# AS_Node_Outputs.net
KiCad netlist of a schematic drawn in Altium Designer
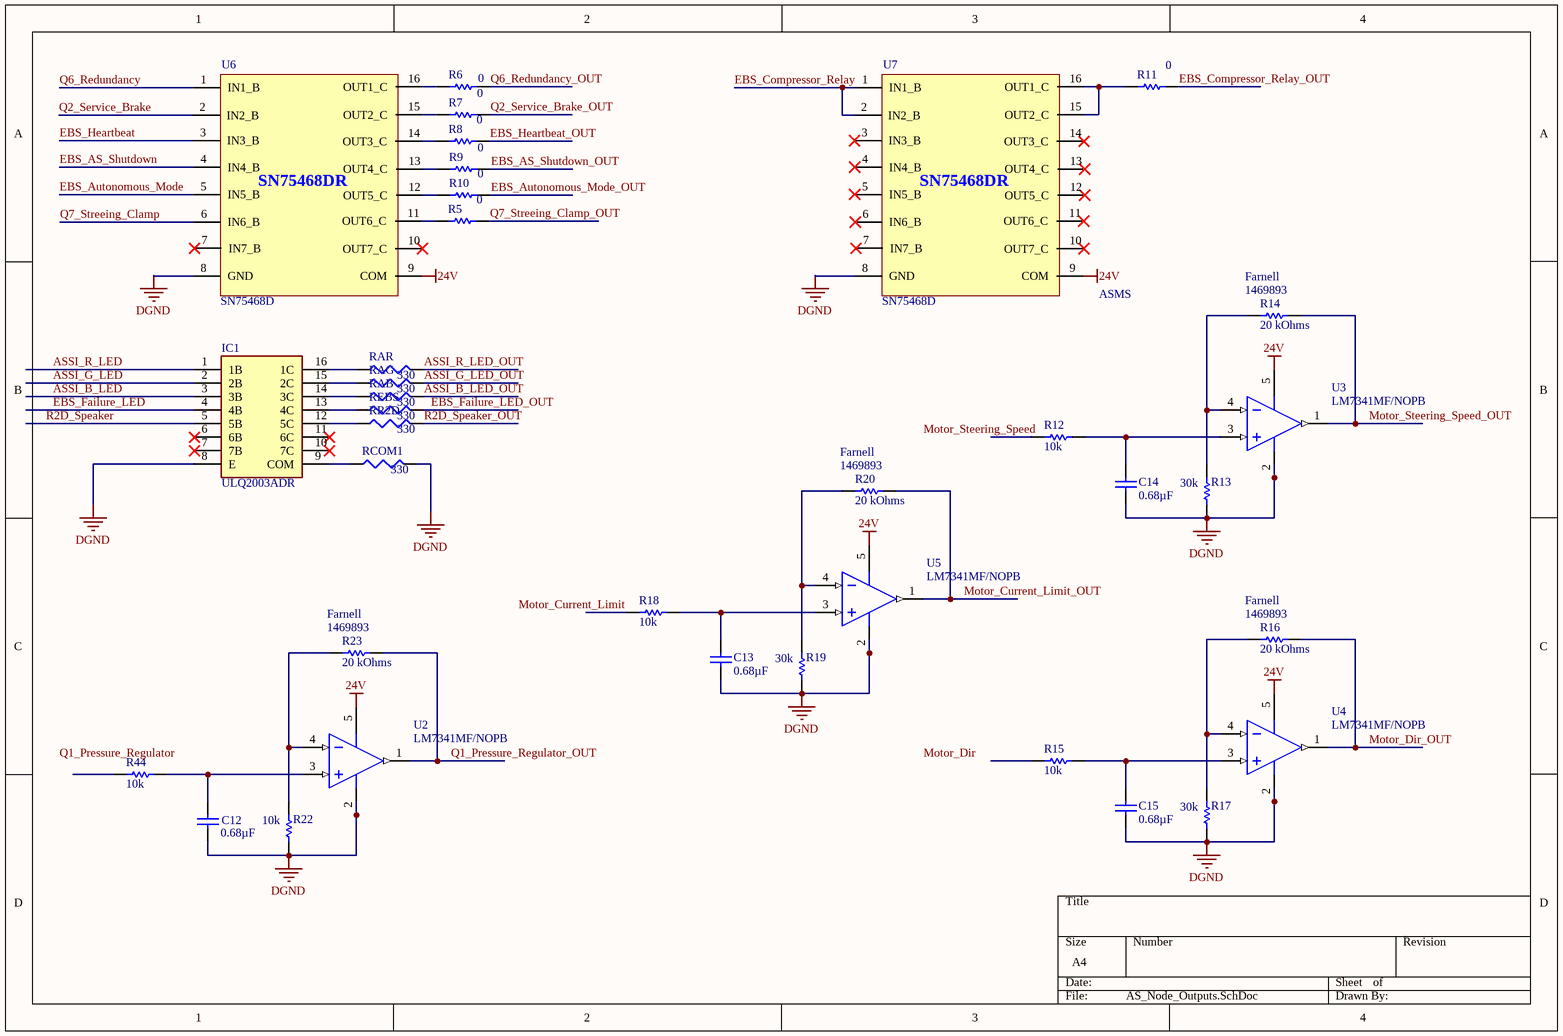
[diagram p0: AS_Node_Outputs.SchDoc]

(export (version "E")
  (design (tool "Eeschema 10.0.6"))
  (components
    (comp (ref "C12")
      (value "0.68µF")
      (footprint "dV_C0805")
      (fields
        (field (name "MANUFACTURER") "KEMET")
        (field (name "MANUFACTURER PART NUMBER") "C0805C684J3NACTU")
      )
      (libsource (lib "altium-import") (part "root_1_Cap_"))
    )
    (comp (ref "C13")
      (value "0.68µF")
      (footprint "dV_C0805")
      (fields
        (field (name "MANUFACTURER") "KEMET")
        (field (name "MANUFACTURER PART NUMBER") "C0805C684J3NACTU")
      )
      (libsource (lib "altium-import") (part "root_1_Cap_"))
    )
    (comp (ref "C14")
      (value "0.68µF")
      (footprint "dV_C0805")
      (fields
        (field (name "MANUFACTURER") "KEMET")
        (field (name "MANUFACTURER PART NUMBER") "C0805C684J3NACTU")
      )
      (libsource (lib "altium-import") (part "root_1_Cap_"))
    )
    (comp (ref "C15")
      (value "0.68µF")
      (footprint "dV_C0805")
      (fields
        (field (name "MANUFACTURER") "KEMET")
        (field (name "MANUFACTURER PART NUMBER") "C0805C684J3NACTU")
      )
      (libsource (lib "altium-import") (part "root_1_Cap_"))
    )
    (comp (ref "IC1")
      (value "ULQ2003ADR")
      (footprint "SamacSys:SOIC127P600X175-16N")
      (description "Integrated Circuit")
      (fields (field (name "MOUSER PART NUMBER") "595-ULQ2003ADR") (field (name "RS PART NUMBER") "6658696P"))
      (libsource (lib "*") (part "ULQ2003ADR"))
    )
    (comp (ref "R5")
      (value "0")
      (footprint "dV_R0805")
      (fields
        (field (name "MANUFACTURER") "PANASONIC ELECTRONIC COMPONENTS")
        (field (name "MANUFACTURER PART NUMBER") "ERJ6GEY0R00V")
      )
      (libsource (lib "altium-import") (part "root_0_Res1_"))
    )
    (comp (ref "R6")
      (value "0")
      (footprint "dV_R0805")
      (fields
        (field (name "MANUFACTURER") "PANASONIC ELECTRONIC COMPONENTS")
        (field (name "MANUFACTURER PART NUMBER") "ERJ6GEY0R00V")
      )
      (libsource (lib "altium-import") (part "root_0_Res1_"))
    )
    (comp (ref "R7")
      (value "0")
      (footprint "dV_R0805")
      (fields
        (field (name "MANUFACTURER") "PANASONIC ELECTRONIC COMPONENTS")
        (field (name "MANUFACTURER PART NUMBER") "ERJ6GEY0R00V")
      )
      (libsource (lib "altium-import") (part "root_0_Res1_"))
    )
    (comp (ref "R8")
      (value "0")
      (footprint "dV_R0805")
      (fields
        (field (name "MANUFACTURER") "PANASONIC ELECTRONIC COMPONENTS")
        (field (name "MANUFACTURER PART NUMBER") "ERJ6GEY0R00V")
      )
      (libsource (lib "altium-import") (part "root_0_Res1_"))
    )
    (comp (ref "R9")
      (value "0")
      (footprint "dV_R0805")
      (fields
        (field (name "MANUFACTURER") "PANASONIC ELECTRONIC COMPONENTS")
        (field (name "MANUFACTURER PART NUMBER") "ERJ6GEY0R00V")
      )
      (libsource (lib "altium-import") (part "root_0_Res1_"))
    )
    (comp (ref "R10")
      (value "0")
      (footprint "dV_R0805")
      (fields
        (field (name "MANUFACTURER") "PANASONIC ELECTRONIC COMPONENTS")
        (field (name "MANUFACTURER PART NUMBER") "ERJ6GEY0R00V")
      )
      (libsource (lib "altium-import") (part "root_0_Res1_"))
    )
    (comp (ref "R11")
      (value "0")
      (footprint "dV_R0805")
      (fields
        (field (name "MANUFACTURER") "PANASONIC ELECTRONIC COMPONENTS")
        (field (name "MANUFACTURER PART NUMBER") "ERJ6GEY0R00V")
      )
      (libsource (lib "altium-import") (part "root_0_Res1_"))
    )
    (comp (ref "R12")
      (value "10k")
      (footprint "dV_R0805")
      (fields
        (field (name "MANUFACTURER") "PANASONIC ELECTRONIC COMPONENTS")
        (field (name "MANUFACTURER PART NUMBER") "ERA6AEB103V")
      )
      (libsource (lib "altium-import") (part "root_0_Res1_"))
    )
    (comp (ref "R13")
      (value "30k")
      (footprint "dV_R0805")
      (fields
        (field (name "MANUFACTURER") "Panasonic")
        (field (name "MANUFACTURER PART NUMBER") "ERA-6AEB303V")
      )
      (libsource (lib "altium-import") (part "root_3_Res1_"))
    )
    (comp (ref "R14")
      (value "20 kOhms")
      (footprint "dV_R0805")
      (fields
        (field (name "MANUFACTURER PART NUMBER") "CRCW080520K0FKEA")
        (field (name "MANUFACTURER") "Vishay")
        (field (name "SUPPLIER PART NUMBER") "1469893")
        (field (name "TOLERANCE") "1 %")
        (field (name "SUPPLIER") "Farnell")
      )
      (libsource (lib "altium-import") (part "root_0_Res1_"))
    )
    (comp (ref "R15")
      (value "10k")
      (footprint "dV_R0805")
      (fields
        (field (name "MANUFACTURER") "PANASONIC ELECTRONIC COMPONENTS")
        (field (name "MANUFACTURER PART NUMBER") "ERA6AEB103V")
      )
      (libsource (lib "altium-import") (part "root_0_Res1_"))
    )
    (comp (ref "R16")
      (value "20 kOhms")
      (footprint "dV_R0805")
      (fields
        (field (name "MANUFACTURER PART NUMBER") "CRCW080520K0FKEA")
        (field (name "MANUFACTURER") "Vishay")
        (field (name "SUPPLIER PART NUMBER") "1469893")
        (field (name "TOLERANCE") "1 %")
        (field (name "SUPPLIER") "Farnell")
      )
      (libsource (lib "altium-import") (part "root_0_Res1_"))
    )
    (comp (ref "R17")
      (value "30k")
      (footprint "dV_R0805")
      (fields
        (field (name "MANUFACTURER") "Panasonic")
        (field (name "MANUFACTURER PART NUMBER") "ERA-6AEB303V")
      )
      (libsource (lib "altium-import") (part "root_3_Res1_"))
    )
    (comp (ref "R18")
      (value "10k")
      (footprint "dV_R0805")
      (fields
        (field (name "MANUFACTURER") "PANASONIC ELECTRONIC COMPONENTS")
        (field (name "MANUFACTURER PART NUMBER") "ERA6AEB103V")
      )
      (libsource (lib "altium-import") (part "root_0_Res1_"))
    )
    (comp (ref "R19")
      (value "30k")
      (footprint "dV_R0805")
      (fields
        (field (name "MANUFACTURER") "Panasonic")
        (field (name "MANUFACTURER PART NUMBER") "ERA-6AEB303V")
      )
      (libsource (lib "altium-import") (part "root_3_Res1_"))
    )
    (comp (ref "R20")
      (value "20 kOhms")
      (footprint "dV_R0805")
      (fields
        (field (name "MANUFACTURER PART NUMBER") "CRCW080520K0FKEA")
        (field (name "MANUFACTURER") "Vishay")
        (field (name "SUPPLIER PART NUMBER") "1469893")
        (field (name "TOLERANCE") "1 %")
        (field (name "SUPPLIER") "Farnell")
      )
      (libsource (lib "altium-import") (part "root_0_Res1_"))
    )
    (comp (ref "R22")
      (value "10k")
      (footprint "dV_R0805")
      (fields
        (field (name "MANUFACTURER") "PANASONIC ELECTRONIC COMPONENTS")
        (field (name "MANUFACTURER PART NUMBER") "ERA6AEB103V")
      )
      (libsource (lib "altium-import") (part "root_3_Res1_"))
    )
    (comp (ref "R23")
      (value "20 kOhms")
      (footprint "dV_R0805")
      (fields
        (field (name "MANUFACTURER PART NUMBER") "CRCW080520K0FKEA")
        (field (name "MANUFACTURER") "Vishay")
        (field (name "SUPPLIER PART NUMBER") "1469893")
        (field (name "TOLERANCE") "1 %")
        (field (name "SUPPLIER") "Farnell")
      )
      (libsource (lib "altium-import") (part "root_0_Res1_"))
    )
    (comp (ref "R44")
      (value "10k")
      (footprint "dV_R0805")
      (fields
        (field (name "MANUFACTURER") "PANASONIC ELECTRONIC COMPONENTS")
        (field (name "MANUFACTURER PART NUMBER") "ERA6AEB103V")
      )
      (libsource (lib "altium-import") (part "root_0_Res1_"))
    )
    (comp (ref "RAB")
      (value "330")
      (footprint "SMD-0805-RES")
      (description "Resistor")
      (fields (field (name "Comment") "Res3") (field (name "PUBLISHER") "Altium Limited"))
      (libsource (lib "Miscellaneous Devices") (part "Res3"))
    )
    (comp (ref "RAG")
      (value "330")
      (footprint "SMD-0805-RES")
      (description "Resistor")
      (fields (field (name "Comment") "Res3") (field (name "PUBLISHER") "Altium Limited"))
      (libsource (lib "Miscellaneous Devices") (part "Res3"))
    )
    (comp (ref "RAR")
      (value "330")
      (footprint "SMD-0805-RES")
      (description "Resistor")
      (fields (field (name "Comment") "Res3") (field (name "PUBLISHER") "Altium Limited"))
      (libsource (lib "Miscellaneous Devices") (part "Res3"))
    )
    (comp (ref "RCOM1")
      (value "330")
      (footprint "SMD-0805-RES")
      (description "Resistor")
      (fields (field (name "Comment") "Res3") (field (name "PUBLISHER") "Altium Limited"))
      (libsource (lib "Miscellaneous Devices") (part "Res3"))
    )
    (comp (ref "REBS")
      (value "330")
      (footprint "SMD-0805-RES")
      (description "Resistor")
      (fields (field (name "Comment") "Res3") (field (name "PUBLISHER") "Altium Limited"))
      (libsource (lib "Miscellaneous Devices") (part "Res3"))
    )
    (comp (ref "RR2D")
      (value "330")
      (footprint "SMD-0805-RES")
      (description "Resistor")
      (fields (field (name "Comment") "Res3") (field (name "PUBLISHER") "Altium Limited"))
      (libsource (lib "Miscellaneous Devices") (part "Res3"))
    )
    (comp (ref "U2")
      (value "LM7341MF/NOPB")
      (footprint "SOT-23-5")
      (fields (field (name "MANUFACTURER") "TEXAS INSTRUMENTS"))
      (libsource (lib "TI Amplifiers and Linear Operational Amplifier Precision Amplifier Part Two") (part "TLV2371IDBVT"))
    )
    (comp (ref "U3")
      (value "LM7341MF/NOPB")
      (footprint "SOT-23-5")
      (fields (field (name "MANUFACTURER") "TEXAS INSTRUMENTS"))
      (libsource (lib "TI Amplifiers and Linear Operational Amplifier Precision Amplifier Part Two") (part "TLV2371IDBVT"))
    )
    (comp (ref "U4")
      (value "LM7341MF/NOPB")
      (footprint "SOT-23-5")
      (fields (field (name "MANUFACTURER") "TEXAS INSTRUMENTS"))
      (libsource (lib "TI Amplifiers and Linear Operational Amplifier Precision Amplifier Part Two") (part "TLV2371IDBVT"))
    )
    (comp (ref "U5")
      (value "LM7341MF/NOPB")
      (footprint "SOT-23-5")
      (fields (field (name "MANUFACTURER") "TEXAS INSTRUMENTS"))
      (libsource (lib "TI Amplifiers and Linear Operational Amplifier Precision Amplifier Part Two") (part "TLV2371IDBVT"))
    )
    (comp (ref "U6")
      (value "SN75468D")
      (footprint "ULQ2001")
      (fields (field (name "MANUFACTURER") "Texas Instruments"))
      (libsource (lib "nodes library") (part "SN75468DR"))
    )
    (comp (ref "U7")
      (value "SN75468D")
      (footprint "ULQ2001")
      (fields (field (name "MANUFACTURER") "Texas Instruments"))
      (libsource (lib "nodes library") (part "SN75468DR"))
    )
  )
  (nets
    (net (code "2") (name "/ASSI_B_LED") (class "Default")
      (node (ref "IC1") (pin "3") (pinfunction "3B_3") (pintype "passive"))
    )
    (net (code "3") (name "/ASSI_B_LED_OUT") (class "Default")
      (node (ref "RAB") (pin "2") (pinfunction "2_2") (pintype "passive"))
    )
    (net (code "4") (name "/ASSI_G_LED") (class "Default")
      (node (ref "IC1") (pin "2") (pinfunction "2B_2") (pintype "passive"))
    )
    (net (code "5") (name "/ASSI_G_LED_OUT") (class "Default")
      (node (ref "RAG") (pin "2") (pinfunction "2_2") (pintype "passive"))
    )
    (net (code "6") (name "/ASSI_R_LED") (class "Default")
      (node (ref "IC1") (pin "1") (pinfunction "1B_1") (pintype "passive"))
    )
    (net (code "7") (name "/ASSI_R_LED_OUT") (class "Default")
      (node (ref "RAR") (pin "2") (pinfunction "2_2") (pintype "passive"))
    )
    (net (code "8") (name "/EBS_AS_Shutdown") (class "Default")
      (node (ref "U6") (pin "4") (pinfunction "IN4_B_4") (pintype "passive"))
    )
    (net (code "9") (name "/EBS_AS_Shutdown_OUT") (class "Default")
      (node (ref "R9") (pin "2") (pinfunction "2_2") (pintype "passive"))
    )
    (net (code "10") (name "/EBS_Autonomous_Mode") (class "Default")
      (node (ref "U6") (pin "5") (pinfunction "IN5_B_5") (pintype "passive"))
    )
    (net (code "11") (name "/EBS_Autonomous_Mode_OUT") (class "Default")
      (node (ref "R10") (pin "2") (pinfunction "2_2") (pintype "passive"))
    )
    (net (code "12") (name "/EBS_Compressor_Relay") (class "Default")
      (node (ref "U7") (pin "1") (pinfunction "IN1_B_1") (pintype "passive"))
      (node (ref "U7") (pin "2") (pinfunction "IN2_B_2") (pintype "passive"))
    )
    (net (code "13") (name "/EBS_Compressor_Relay_OUT") (class "Default")
      (node (ref "R11") (pin "2") (pinfunction "2_2") (pintype "passive"))
    )
    (net (code "14") (name "/EBS_Failure_LED") (class "Default")
      (node (ref "IC1") (pin "4") (pinfunction "4B_4") (pintype "passive"))
    )
    (net (code "15") (name "/EBS_Failure_LED_OUT") (class "Default")
      (node (ref "REBS") (pin "2") (pinfunction "2_2") (pintype "passive"))
    )
    (net (code "16") (name "/EBS_Heartbeat") (class "Default")
      (node (ref "U6") (pin "3") (pinfunction "IN3_B_3") (pintype "passive"))
    )
    (net (code "17") (name "/EBS_Heartbeat_OUT") (class "Default")
      (node (ref "R8") (pin "2") (pinfunction "2_2") (pintype "passive"))
    )
    (net (code "19") (name "/Motor_Current_Limit_OUT") (class "Default")
      (node (ref "R20") (pin "2") (pinfunction "2_2") (pintype "passive"))
      (node (ref "U5") (pin "1") (pinfunction "OUT_1") (pintype "output"))
    )
    (net (code "21") (name "/Motor_Dir_OUT") (class "Default")
      (node (ref "R16") (pin "2") (pinfunction "2_2") (pintype "passive"))
      (node (ref "U4") (pin "1") (pinfunction "OUT_1") (pintype "output"))
    )
    (net (code "23") (name "/Motor_Steering_Speed_OUT") (class "Default")
      (node (ref "R14") (pin "2") (pinfunction "2_2") (pintype "passive"))
      (node (ref "U3") (pin "1") (pinfunction "OUT_1") (pintype "output"))
    )
    (net (code "25") (name "/Q1_Pressure_Regulator_OUT") (class "Default")
      (node (ref "R23") (pin "2") (pinfunction "2_2") (pintype "passive"))
      (node (ref "U2") (pin "1") (pinfunction "OUT_1") (pintype "output"))
    )
    (net (code "26") (name "/Q2_Service_Brake") (class "Default")
      (node (ref "U6") (pin "2") (pinfunction "IN2_B_2") (pintype "passive"))
    )
    (net (code "27") (name "/Q2_Service_Brake_OUT") (class "Default")
      (node (ref "R7") (pin "2") (pinfunction "2_2") (pintype "passive"))
    )
    (net (code "28") (name "/Q6_Redundancy") (class "Default")
      (node (ref "U6") (pin "1") (pinfunction "IN1_B_1") (pintype "passive"))
    )
    (net (code "29") (name "/Q6_Redundancy_OUT") (class "Default")
      (node (ref "R6") (pin "2") (pinfunction "2_2") (pintype "passive"))
    )
    (net (code "30") (name "/Q7_Streeing_Clamp") (class "Default")
      (node (ref "U6") (pin "6") (pinfunction "IN6_B_6") (pintype "passive"))
    )
    (net (code "31") (name "/Q7_Streeing_Clamp_OUT") (class "Default")
      (node (ref "R5") (pin "2") (pinfunction "2_2") (pintype "passive"))
    )
    (net (code "32") (name "/R2D_Speaker") (class "Default")
      (node (ref "IC1") (pin "5") (pinfunction "5B_5") (pintype "passive"))
    )
    (net (code "33") (name "/R2D_Speaker_OUT") (class "Default")
      (node (ref "RR2D") (pin "2") (pinfunction "2_2") (pintype "passive"))
    )
    (net (code "34") (name "24V") (class "Default")
      (node (ref "U2") (pin "5") (pinfunction "VDD_5") (pintype "power_in"))
      (node (ref "U3") (pin "5") (pinfunction "VDD_5") (pintype "power_in"))
      (node (ref "U4") (pin "5") (pinfunction "VDD_5") (pintype "power_in"))
      (node (ref "U5") (pin "5") (pinfunction "VDD_5") (pintype "power_in"))
      (node (ref "U6") (pin "9") (pinfunction "COM_9") (pintype "passive"))
      (node (ref "U7") (pin "9") (pinfunction "COM_9") (pintype "passive"))
    )
    (net (code "35") (name "DGND") (class "Default")
      (node (ref "C12") (pin "1") (pinfunction "1_1") (pintype "passive"))
      (node (ref "C13") (pin "1") (pinfunction "1_1") (pintype "passive"))
      (node (ref "C14") (pin "1") (pinfunction "1_1") (pintype "passive"))
      (node (ref "C15") (pin "1") (pinfunction "1_1") (pintype "passive"))
      (node (ref "IC1") (pin "8") (pinfunction "E_8") (pintype "passive"))
      (node (ref "R13") (pin "2") (pinfunction "2_2") (pintype "passive"))
      (node (ref "R17") (pin "2") (pinfunction "2_2") (pintype "passive"))
      (node (ref "R19") (pin "2") (pinfunction "2_2") (pintype "passive"))
      (node (ref "R22") (pin "2") (pinfunction "2_2") (pintype "passive"))
      (node (ref "RCOM1") (pin "2") (pinfunction "2_2") (pintype "passive"))
      (node (ref "U2") (pin "2") (pinfunction "GND_2") (pintype "power_in"))
      (node (ref "U3") (pin "2") (pinfunction "GND_2") (pintype "power_in"))
      (node (ref "U4") (pin "2") (pinfunction "GND_2") (pintype "power_in"))
      (node (ref "U5") (pin "2") (pinfunction "GND_2") (pintype "power_in"))
      (node (ref "U6") (pin "8") (pinfunction "GND_8") (pintype "passive"))
      (node (ref "U7") (pin "8") (pinfunction "GND_8") (pintype "passive"))
    )
    (net (code "36") (name "Net-(IC1-1C)") (class "Default")
      (node (ref "IC1") (pin "16") (pinfunction "1C_16") (pintype "passive"))
      (node (ref "RAR") (pin "1") (pinfunction "1_1") (pintype "passive"))
    )
    (net (code "37") (name "Net-(IC1-2C)") (class "Default")
      (node (ref "IC1") (pin "15") (pinfunction "2C_15") (pintype "passive"))
      (node (ref "RAG") (pin "1") (pinfunction "1_1") (pintype "passive"))
    )
    (net (code "38") (name "Net-(IC1-3C)") (class "Default")
      (node (ref "IC1") (pin "14") (pinfunction "3C_14") (pintype "passive"))
      (node (ref "RAB") (pin "1") (pinfunction "1_1") (pintype "passive"))
    )
    (net (code "39") (name "Net-(IC1-4C)") (class "Default")
      (node (ref "IC1") (pin "13") (pinfunction "4C_13") (pintype "passive"))
      (node (ref "REBS") (pin "1") (pinfunction "1_1") (pintype "passive"))
    )
    (net (code "40") (name "Net-(IC1-5C)") (class "Default")
      (node (ref "IC1") (pin "12") (pinfunction "5C_12") (pintype "passive"))
      (node (ref "RR2D") (pin "1") (pinfunction "1_1") (pintype "passive"))
    )
    (net (code "41") (name "Net-(IC1-COM)") (class "Default")
      (node (ref "IC1") (pin "9") (pinfunction "COM_9") (pintype "passive"))
      (node (ref "RCOM1") (pin "1") (pinfunction "1_1") (pintype "passive"))
    )
    (net (code "42") (name "Net-(U2-IN+)") (class "Default")
      (node (ref "C12") (pin "2") (pinfunction "2_2") (pintype "passive"))
      (node (ref "R44") (pin "2") (pinfunction "2_2") (pintype "passive"))
      (node (ref "U2") (pin "3") (pinfunction "IN+_3") (pintype "input"))
    )
    (net (code "43") (name "Net-(U2-IN-)") (class "Default")
      (node (ref "R22") (pin "1") (pinfunction "1_1") (pintype "passive"))
      (node (ref "R23") (pin "1") (pinfunction "1_1") (pintype "passive"))
      (node (ref "U2") (pin "4") (pinfunction "IN-_4") (pintype "input"))
    )
    (net (code "44") (name "Net-(U3-IN+)") (class "Default")
      (node (ref "C14") (pin "2") (pinfunction "2_2") (pintype "passive"))
      (node (ref "R12") (pin "2") (pinfunction "2_2") (pintype "passive"))
      (node (ref "U3") (pin "3") (pinfunction "IN+_3") (pintype "input"))
    )
    (net (code "45") (name "Net-(U3-IN-)") (class "Default")
      (node (ref "R13") (pin "1") (pinfunction "1_1") (pintype "passive"))
      (node (ref "R14") (pin "1") (pinfunction "1_1") (pintype "passive"))
      (node (ref "U3") (pin "4") (pinfunction "IN-_4") (pintype "input"))
    )
    (net (code "46") (name "Net-(U4-IN+)") (class "Default")
      (node (ref "C15") (pin "2") (pinfunction "2_2") (pintype "passive"))
      (node (ref "R15") (pin "2") (pinfunction "2_2") (pintype "passive"))
      (node (ref "U4") (pin "3") (pinfunction "IN+_3") (pintype "input"))
    )
    (net (code "47") (name "Net-(U4-IN-)") (class "Default")
      (node (ref "R16") (pin "1") (pinfunction "1_1") (pintype "passive"))
      (node (ref "R17") (pin "1") (pinfunction "1_1") (pintype "passive"))
      (node (ref "U4") (pin "4") (pinfunction "IN-_4") (pintype "input"))
    )
    (net (code "48") (name "Net-(U5-IN+)") (class "Default")
      (node (ref "C13") (pin "2") (pinfunction "2_2") (pintype "passive"))
      (node (ref "R18") (pin "2") (pinfunction "2_2") (pintype "passive"))
      (node (ref "U5") (pin "3") (pinfunction "IN+_3") (pintype "input"))
    )
    (net (code "49") (name "Net-(U5-IN-)") (class "Default")
      (node (ref "R19") (pin "1") (pinfunction "1_1") (pintype "passive"))
      (node (ref "R20") (pin "1") (pinfunction "1_1") (pintype "passive"))
      (node (ref "U5") (pin "4") (pinfunction "IN-_4") (pintype "input"))
    )
    (net (code "50") (name "Net-(U6-OUT1_C)") (class "Default")
      (node (ref "R6") (pin "1") (pinfunction "1_1") (pintype "passive"))
      (node (ref "U6") (pin "16") (pinfunction "OUT1_C_16") (pintype "passive"))
    )
    (net (code "51") (name "Net-(U6-OUT2_C)") (class "Default")
      (node (ref "R7") (pin "1") (pinfunction "1_1") (pintype "passive"))
      (node (ref "U6") (pin "15") (pinfunction "OUT2_C_15") (pintype "passive"))
    )
    (net (code "52") (name "Net-(U6-OUT3_C)") (class "Default")
      (node (ref "R8") (pin "1") (pinfunction "1_1") (pintype "passive"))
      (node (ref "U6") (pin "14") (pinfunction "OUT3_C_14") (pintype "passive"))
    )
    (net (code "53") (name "Net-(U6-OUT4_C)") (class "Default")
      (node (ref "R9") (pin "1") (pinfunction "1_1") (pintype "passive"))
      (node (ref "U6") (pin "13") (pinfunction "OUT4_C_13") (pintype "passive"))
    )
    (net (code "54") (name "Net-(U6-OUT5_C)") (class "Default")
      (node (ref "R10") (pin "1") (pinfunction "1_1") (pintype "passive"))
      (node (ref "U6") (pin "12") (pinfunction "OUT5_C_12") (pintype "passive"))
    )
    (net (code "55") (name "Net-(U6-OUT6_C)") (class "Default")
      (node (ref "R5") (pin "1") (pinfunction "1_1") (pintype "passive"))
      (node (ref "U6") (pin "11") (pinfunction "OUT6_C_11") (pintype "passive"))
    )
    (net (code "56") (name "Net-(U7-OUT1_C)") (class "Default")
      (node (ref "R11") (pin "1") (pinfunction "1_1") (pintype "passive"))
      (node (ref "U7") (pin "15") (pinfunction "OUT2_C_15") (pintype "passive"))
      (node (ref "U7") (pin "16") (pinfunction "OUT1_C_16") (pintype "passive"))
    )
    (net (code "57") (name "unconnected-(IC1-6B-Pad6)") (class "Default")
      (node (ref "IC1") (pin "6") (pinfunction "6B_6") (pintype "passive+no_connect"))
    )
    (net (code "58") (name "unconnected-(IC1-6C-Pad11)") (class "Default")
      (node (ref "IC1") (pin "11") (pinfunction "6C_11") (pintype "passive+no_connect"))
    )
    (net (code "59") (name "unconnected-(IC1-7B-Pad7)") (class "Default")
      (node (ref "IC1") (pin "7") (pinfunction "7B_7") (pintype "passive+no_connect"))
    )
    (net (code "60") (name "unconnected-(IC1-7C-Pad10)") (class "Default")
      (node (ref "IC1") (pin "10") (pinfunction "7C_10") (pintype "passive+no_connect"))
    )
    (net (code "61") (name "unconnected-(R12-Pad1)") (class "Default")
      (node (ref "R12") (pin "1") (pinfunction "1_1") (pintype "passive"))
    )
    (net (code "62") (name "unconnected-(R15-Pad1)") (class "Default")
      (node (ref "R15") (pin "1") (pinfunction "1_1") (pintype "passive"))
    )
    (net (code "63") (name "unconnected-(R18-Pad1)") (class "Default")
      (node (ref "R18") (pin "1") (pinfunction "1_1") (pintype "passive"))
    )
    (net (code "64") (name "unconnected-(R44-Pad1)") (class "Default")
      (node (ref "R44") (pin "1") (pinfunction "1_1") (pintype "passive"))
    )
    (net (code "65") (name "unconnected-(U6-IN7_B-Pad7)") (class "Default")
      (node (ref "U6") (pin "7") (pinfunction "IN7_B_7") (pintype "passive+no_connect"))
    )
    (net (code "66") (name "unconnected-(U6-OUT7_C-Pad10)") (class "Default")
      (node (ref "U6") (pin "10") (pinfunction "OUT7_C_10") (pintype "passive+no_connect"))
    )
    (net (code "67") (name "unconnected-(U7-IN3_B-Pad3)") (class "Default")
      (node (ref "U7") (pin "3") (pinfunction "IN3_B_3") (pintype "passive+no_connect"))
    )
    (net (code "68") (name "unconnected-(U7-IN4_B-Pad4)") (class "Default")
      (node (ref "U7") (pin "4") (pinfunction "IN4_B_4") (pintype "passive+no_connect"))
    )
    (net (code "69") (name "unconnected-(U7-IN5_B-Pad5)") (class "Default")
      (node (ref "U7") (pin "5") (pinfunction "IN5_B_5") (pintype "passive+no_connect"))
    )
    (net (code "70") (name "unconnected-(U7-IN6_B-Pad6)") (class "Default")
      (node (ref "U7") (pin "6") (pinfunction "IN6_B_6") (pintype "passive+no_connect"))
    )
    (net (code "71") (name "unconnected-(U7-IN7_B-Pad7)") (class "Default")
      (node (ref "U7") (pin "7") (pinfunction "IN7_B_7") (pintype "passive+no_connect"))
    )
    (net (code "72") (name "unconnected-(U7-OUT3_C-Pad14)") (class "Default")
      (node (ref "U7") (pin "14") (pinfunction "OUT3_C_14") (pintype "passive+no_connect"))
    )
    (net (code "73") (name "unconnected-(U7-OUT4_C-Pad13)") (class "Default")
      (node (ref "U7") (pin "13") (pinfunction "OUT4_C_13") (pintype "passive+no_connect"))
    )
    (net (code "74") (name "unconnected-(U7-OUT5_C-Pad12)") (class "Default")
      (node (ref "U7") (pin "12") (pinfunction "OUT5_C_12") (pintype "passive+no_connect"))
    )
    (net (code "75") (name "unconnected-(U7-OUT6_C-Pad11)") (class "Default")
      (node (ref "U7") (pin "11") (pinfunction "OUT6_C_11") (pintype "passive+no_connect"))
    )
    (net (code "76") (name "unconnected-(U7-OUT7_C-Pad10)") (class "Default")
      (node (ref "U7") (pin "10") (pinfunction "OUT7_C_10") (pintype "passive+no_connect"))
    )
  )
)
